# i2c_adc.net
KiCad netlist of a schematic drawn in EAGLE
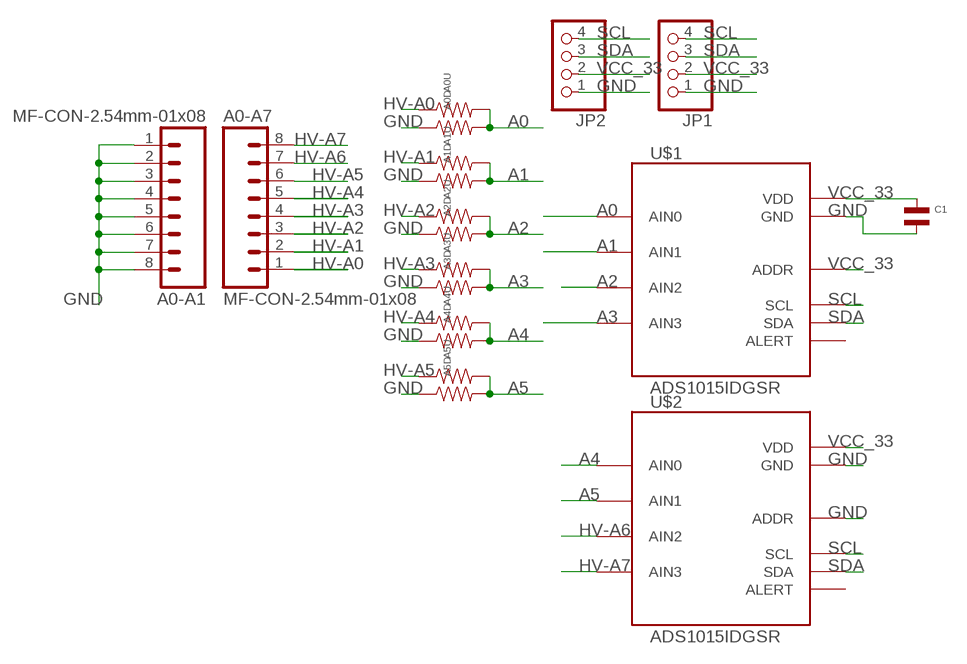
[diagram p0: schematic, sheet 1]

(export (version "E")
  (design (tool "Eeschema 10.0.6"))
  (components
    (comp (ref "A0-A1")
      (value "MF-CON-2.54mm-01x08")
      (footprint "eagle-import:1X08")
      (libsource (lib "eagle-import") (part "M081X08"))
    )
    (comp (ref "A0-A7")
      (value "MF-CON-2.54mm-01x08")
      (footprint "eagle-import:1X08")
      (libsource (lib "eagle-import") (part "M081X08"))
    )
    (comp (ref "A0D")
      (value "RESISTOR_0603")
      (footprint "eagle-import:R0603")
      (libsource (lib "eagle-import") (part "RESISTOR_0603"))
    )
    (comp (ref "A0U")
      (value "RESISTOR_0603")
      (footprint "eagle-import:R0603")
      (libsource (lib "eagle-import") (part "RESISTOR_0603"))
    )
    (comp (ref "A1D")
      (value "RESISTOR_0603")
      (footprint "eagle-import:R0603")
      (libsource (lib "eagle-import") (part "RESISTOR_0603"))
    )
    (comp (ref "A1U")
      (value "RESISTOR_0603")
      (footprint "eagle-import:R0603")
      (libsource (lib "eagle-import") (part "RESISTOR_0603"))
    )
    (comp (ref "A2D")
      (value "RESISTOR_0603")
      (footprint "eagle-import:R0603")
      (libsource (lib "eagle-import") (part "RESISTOR_0603"))
    )
    (comp (ref "A2U")
      (value "RESISTOR_0603")
      (footprint "eagle-import:R0603")
      (libsource (lib "eagle-import") (part "RESISTOR_0603"))
    )
    (comp (ref "A3D")
      (value "RESISTOR_0603")
      (footprint "eagle-import:R0603")
      (libsource (lib "eagle-import") (part "RESISTOR_0603"))
    )
    (comp (ref "A3U")
      (value "RESISTOR_0603")
      (footprint "eagle-import:R0603")
      (libsource (lib "eagle-import") (part "RESISTOR_0603"))
    )
    (comp (ref "A4D")
      (value "RESISTOR_0603")
      (footprint "eagle-import:R0603")
      (libsource (lib "eagle-import") (part "RESISTOR_0603"))
    )
    (comp (ref "A4U")
      (value "RESISTOR_0603")
      (footprint "eagle-import:R0603")
      (libsource (lib "eagle-import") (part "RESISTOR_0603"))
    )
    (comp (ref "A5D")
      (value "RESISTOR_0603")
      (footprint "eagle-import:R0603")
      (libsource (lib "eagle-import") (part "RESISTOR_0603"))
    )
    (comp (ref "A5U")
      (value "RESISTOR_0603")
      (footprint "eagle-import:R0603")
      (libsource (lib "eagle-import") (part "RESISTOR_0603"))
    )
    (comp (ref "C1")
      (value "CAPACITOR_NP_1206")
      (footprint "eagle-import:C1206")
      (libsource (lib "eagle-import") (part "CAPACITOR_NP_1206"))
    )
    (comp (ref "JP1")
      (value "HEADER-1X41MMPADS")
      (footprint "eagle-import:1X04_1.0MM")
      (libsource (lib "eagle-import") (part "HEADER-1X41MMPADS"))
    )
    (comp (ref "JP2")
      (value "HEADER-1X41MMPADS")
      (footprint "eagle-import:1X04_1.0MM")
      (libsource (lib "eagle-import") (part "HEADER-1X41MMPADS"))
    )
    (comp (ref "U$1")
      (value "ADS1015IDGSR")
      (footprint "eagle-import:MSOP10_0.5")
      (libsource (lib "eagle-import") (part "ADS1015IDGT"))
    )
    (comp (ref "U$2")
      (value "ADS1015IDGSR")
      (footprint "eagle-import:MSOP10_0.5")
      (libsource (lib "eagle-import") (part "ADS1015IDGT"))
    )
  )
  (nets
    (net (code "1") (name "/A0") (class "Default")
      (node (ref "A0D") (pin "P$2") (pinfunction "P$2_P$2") (pintype "passive"))
      (node (ref "A0U") (pin "P$2") (pinfunction "P$2_P$2") (pintype "passive"))
      (node (ref "U$1") (pin "4") (pinfunction "AIN0_4") (pintype "input"))
    )
    (net (code "2") (name "/A1") (class "Default")
      (node (ref "A1D") (pin "P$2") (pinfunction "P$2_P$2") (pintype "passive"))
      (node (ref "A1U") (pin "P$2") (pinfunction "P$2_P$2") (pintype "passive"))
      (node (ref "U$1") (pin "5") (pinfunction "AIN1_5") (pintype "input"))
    )
    (net (code "3") (name "/A2") (class "Default")
      (node (ref "A2D") (pin "P$2") (pinfunction "P$2_P$2") (pintype "passive"))
      (node (ref "A2U") (pin "P$2") (pinfunction "P$2_P$2") (pintype "passive"))
      (node (ref "U$1") (pin "6") (pinfunction "AIN2_6") (pintype "input"))
    )
    (net (code "4") (name "/A3") (class "Default")
      (node (ref "A3D") (pin "P$2") (pinfunction "P$2_P$2") (pintype "passive"))
      (node (ref "A3U") (pin "P$2") (pinfunction "P$2_P$2") (pintype "passive"))
      (node (ref "U$1") (pin "7") (pinfunction "AIN3_7") (pintype "input"))
    )
    (net (code "5") (name "/A4") (class "Default")
      (node (ref "A4D") (pin "P$2") (pinfunction "P$2_P$2") (pintype "passive"))
      (node (ref "A4U") (pin "P$2") (pinfunction "P$2_P$2") (pintype "passive"))
      (node (ref "U$2") (pin "4") (pinfunction "AIN0_4") (pintype "input"))
    )
    (net (code "6") (name "/A5") (class "Default")
      (node (ref "A5D") (pin "P$2") (pinfunction "P$2_P$2") (pintype "passive"))
      (node (ref "A5U") (pin "P$2") (pinfunction "P$2_P$2") (pintype "passive"))
      (node (ref "U$2") (pin "5") (pinfunction "AIN1_5") (pintype "input"))
    )
    (net (code "7") (name "/GND") (class "Default")
      (node (ref "A0-A1") (pin "1") (pinfunction "1_1") (pintype "passive"))
      (node (ref "A0-A1") (pin "2") (pinfunction "2_2") (pintype "passive"))
      (node (ref "A0-A1") (pin "3") (pinfunction "3_3") (pintype "passive"))
      (node (ref "A0-A1") (pin "4") (pinfunction "4_4") (pintype "passive"))
      (node (ref "A0-A1") (pin "5") (pinfunction "5_5") (pintype "passive"))
      (node (ref "A0-A1") (pin "6") (pinfunction "6_6") (pintype "passive"))
      (node (ref "A0-A1") (pin "7") (pinfunction "7_7") (pintype "passive"))
      (node (ref "A0-A1") (pin "8") (pinfunction "8_8") (pintype "passive"))
      (node (ref "A0D") (pin "P$1") (pinfunction "P$1_P$1") (pintype "passive"))
      (node (ref "A1D") (pin "P$1") (pinfunction "P$1_P$1") (pintype "passive"))
      (node (ref "A2D") (pin "P$1") (pinfunction "P$1_P$1") (pintype "passive"))
      (node (ref "A3D") (pin "P$1") (pinfunction "P$1_P$1") (pintype "passive"))
      (node (ref "A4D") (pin "P$1") (pinfunction "P$1_P$1") (pintype "passive"))
      (node (ref "A5D") (pin "P$1") (pinfunction "P$1_P$1") (pintype "passive"))
      (node (ref "C1") (pin "P$2") (pinfunction "P$2_P$2") (pintype "passive"))
      (node (ref "JP1") (pin "1") (pinfunction "1_1") (pintype "passive"))
      (node (ref "JP2") (pin "1") (pinfunction "1_1") (pintype "passive"))
      (node (ref "U$1") (pin "3") (pinfunction "GND_3") (pintype "power_in"))
      (node (ref "U$2") (pin "1") (pinfunction "ADDR_1") (pintype "input"))
      (node (ref "U$2") (pin "3") (pinfunction "GND_3") (pintype "power_in"))
    )
    (net (code "8") (name "/HV-A0") (class "Default")
      (node (ref "A0-A7") (pin "1") (pinfunction "1_1") (pintype "passive"))
      (node (ref "A0U") (pin "P$1") (pinfunction "P$1_P$1") (pintype "passive"))
    )
    (net (code "9") (name "/HV-A1") (class "Default")
      (node (ref "A0-A7") (pin "2") (pinfunction "2_2") (pintype "passive"))
      (node (ref "A1U") (pin "P$1") (pinfunction "P$1_P$1") (pintype "passive"))
    )
    (net (code "10") (name "/HV-A2") (class "Default")
      (node (ref "A0-A7") (pin "3") (pinfunction "3_3") (pintype "passive"))
      (node (ref "A2U") (pin "P$1") (pinfunction "P$1_P$1") (pintype "passive"))
    )
    (net (code "11") (name "/HV-A3") (class "Default")
      (node (ref "A0-A7") (pin "4") (pinfunction "4_4") (pintype "passive"))
      (node (ref "A3U") (pin "P$1") (pinfunction "P$1_P$1") (pintype "passive"))
    )
    (net (code "12") (name "/HV-A4") (class "Default")
      (node (ref "A0-A7") (pin "5") (pinfunction "5_5") (pintype "passive"))
      (node (ref "A4U") (pin "P$1") (pinfunction "P$1_P$1") (pintype "passive"))
    )
    (net (code "13") (name "/HV-A5") (class "Default")
      (node (ref "A0-A7") (pin "6") (pinfunction "6_6") (pintype "passive"))
      (node (ref "A5U") (pin "P$1") (pinfunction "P$1_P$1") (pintype "passive"))
    )
    (net (code "14") (name "/HV-A6") (class "Default")
      (node (ref "A0-A7") (pin "7") (pinfunction "7_7") (pintype "passive"))
      (node (ref "U$2") (pin "6") (pinfunction "AIN2_6") (pintype "input"))
    )
    (net (code "15") (name "/HV-A7") (class "Default")
      (node (ref "A0-A7") (pin "8") (pinfunction "8_8") (pintype "passive"))
      (node (ref "U$2") (pin "7") (pinfunction "AIN3_7") (pintype "input"))
    )
    (net (code "16") (name "/SCL") (class "Default")
      (node (ref "JP1") (pin "4") (pinfunction "4_4") (pintype "passive"))
      (node (ref "JP2") (pin "4") (pinfunction "4_4") (pintype "passive"))
      (node (ref "U$1") (pin "10") (pinfunction "SCL_10") (pintype "bidirectional"))
      (node (ref "U$2") (pin "10") (pinfunction "SCL_10") (pintype "bidirectional"))
    )
    (net (code "17") (name "/SDA") (class "Default")
      (node (ref "JP1") (pin "3") (pinfunction "3_3") (pintype "passive"))
      (node (ref "JP2") (pin "3") (pinfunction "3_3") (pintype "passive"))
      (node (ref "U$1") (pin "9") (pinfunction "SDA_9") (pintype "bidirectional"))
      (node (ref "U$2") (pin "9") (pinfunction "SDA_9") (pintype "bidirectional"))
    )
    (net (code "18") (name "/VCC_33") (class "Default")
      (node (ref "C1") (pin "P$1") (pinfunction "P$1_P$1") (pintype "passive"))
      (node (ref "JP1") (pin "2") (pinfunction "2_2") (pintype "passive"))
      (node (ref "JP2") (pin "2") (pinfunction "2_2") (pintype "passive"))
      (node (ref "U$1") (pin "1") (pinfunction "ADDR_1") (pintype "input"))
      (node (ref "U$1") (pin "8") (pinfunction "VDD_8") (pintype "power_in"))
      (node (ref "U$2") (pin "8") (pinfunction "VDD_8") (pintype "power_in"))
    )
    (net (code "19") (name "unconnected-(U$1-ALERT-Pad2)") (class "Default")
      (node (ref "U$1") (pin "2") (pinfunction "ALERT_2") (pintype "output"))
    )
    (net (code "20") (name "unconnected-(U$2-ALERT-Pad2)") (class "Default")
      (node (ref "U$2") (pin "2") (pinfunction "ALERT_2") (pintype "output"))
    )
  )
)
